# Underwater-Camera-v2_0.net
KiCad netlist of a schematic drawn in EAGLE
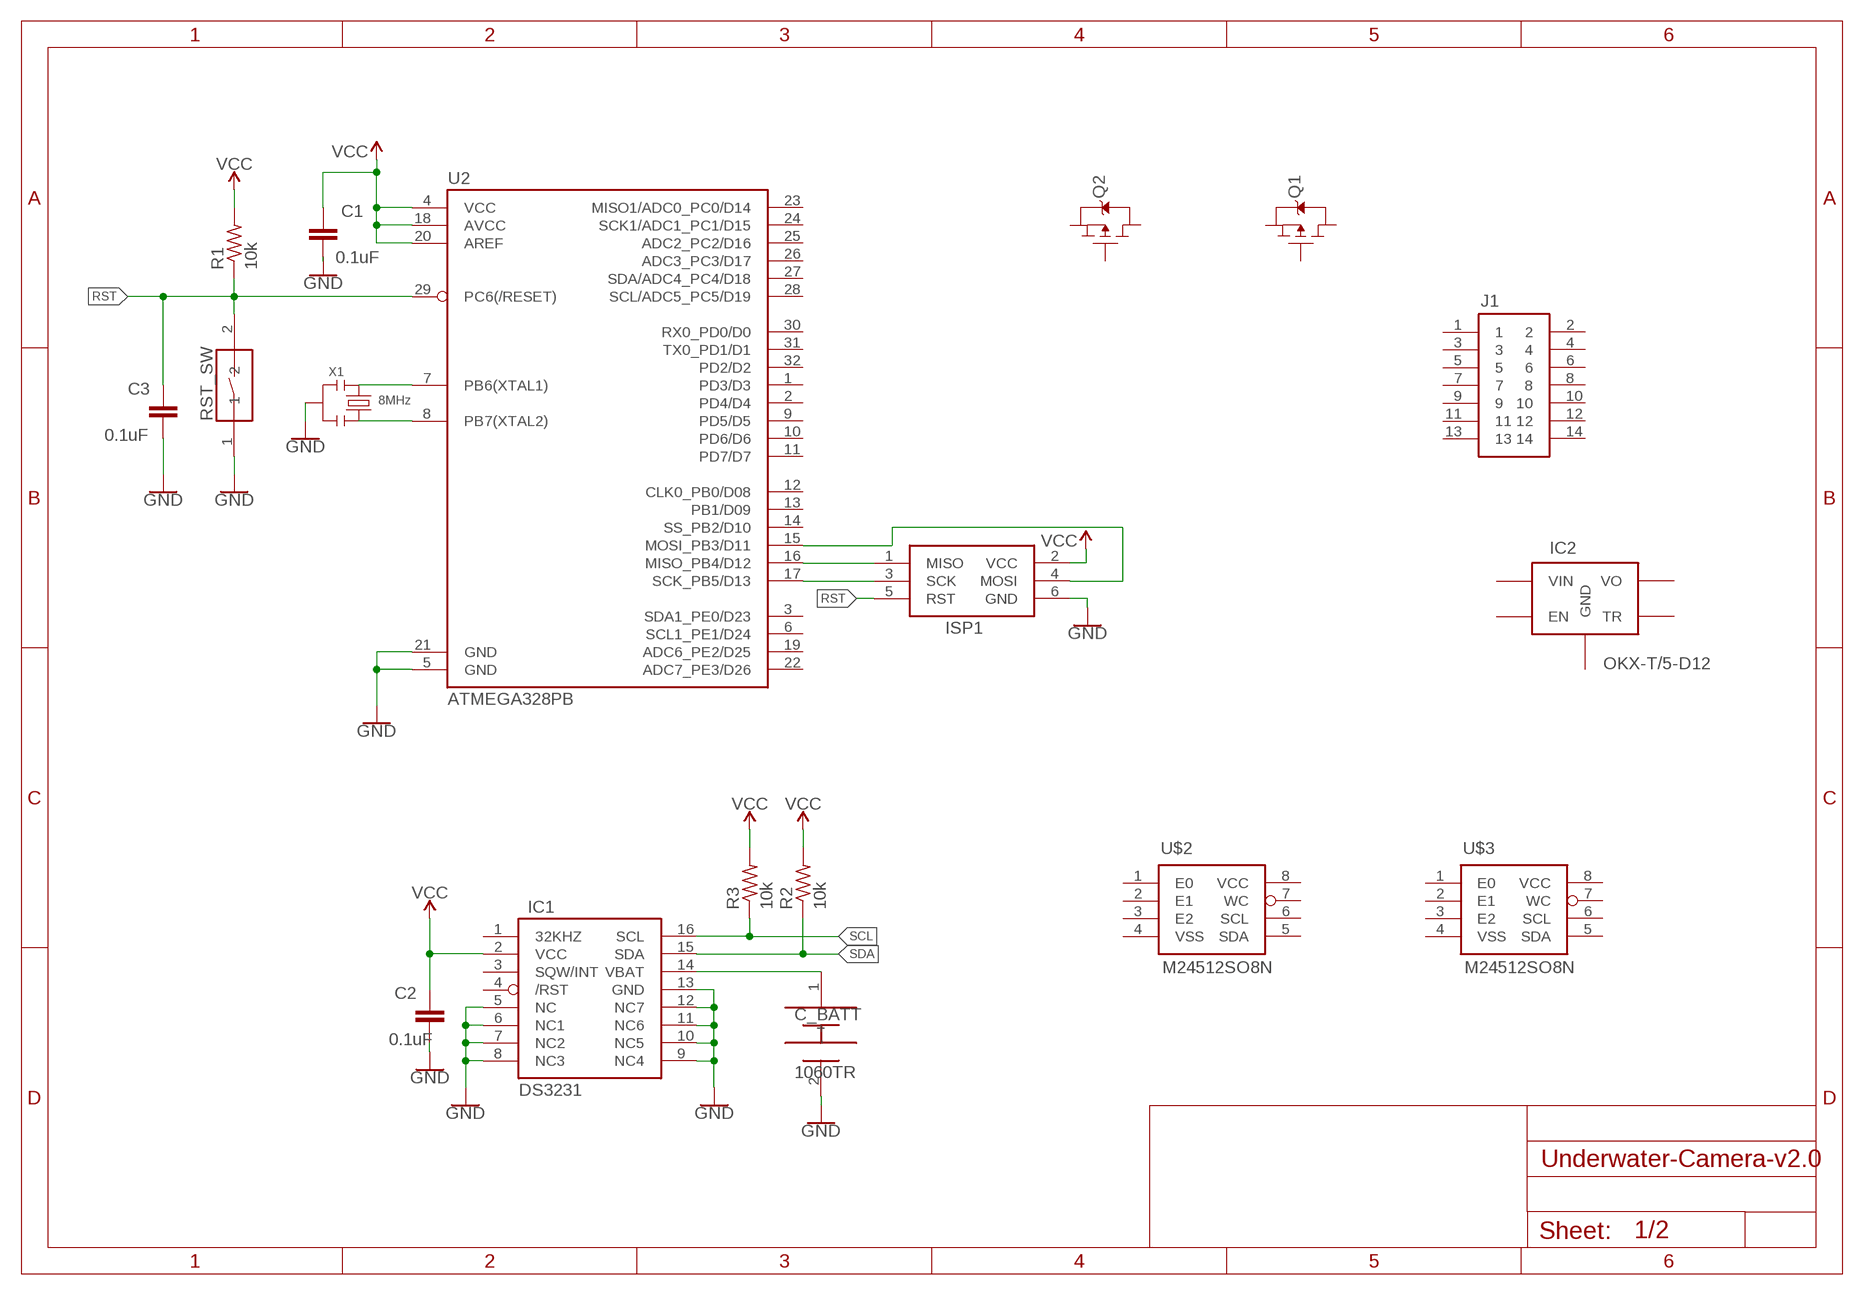
[diagram p0: schematic, sheet 1]
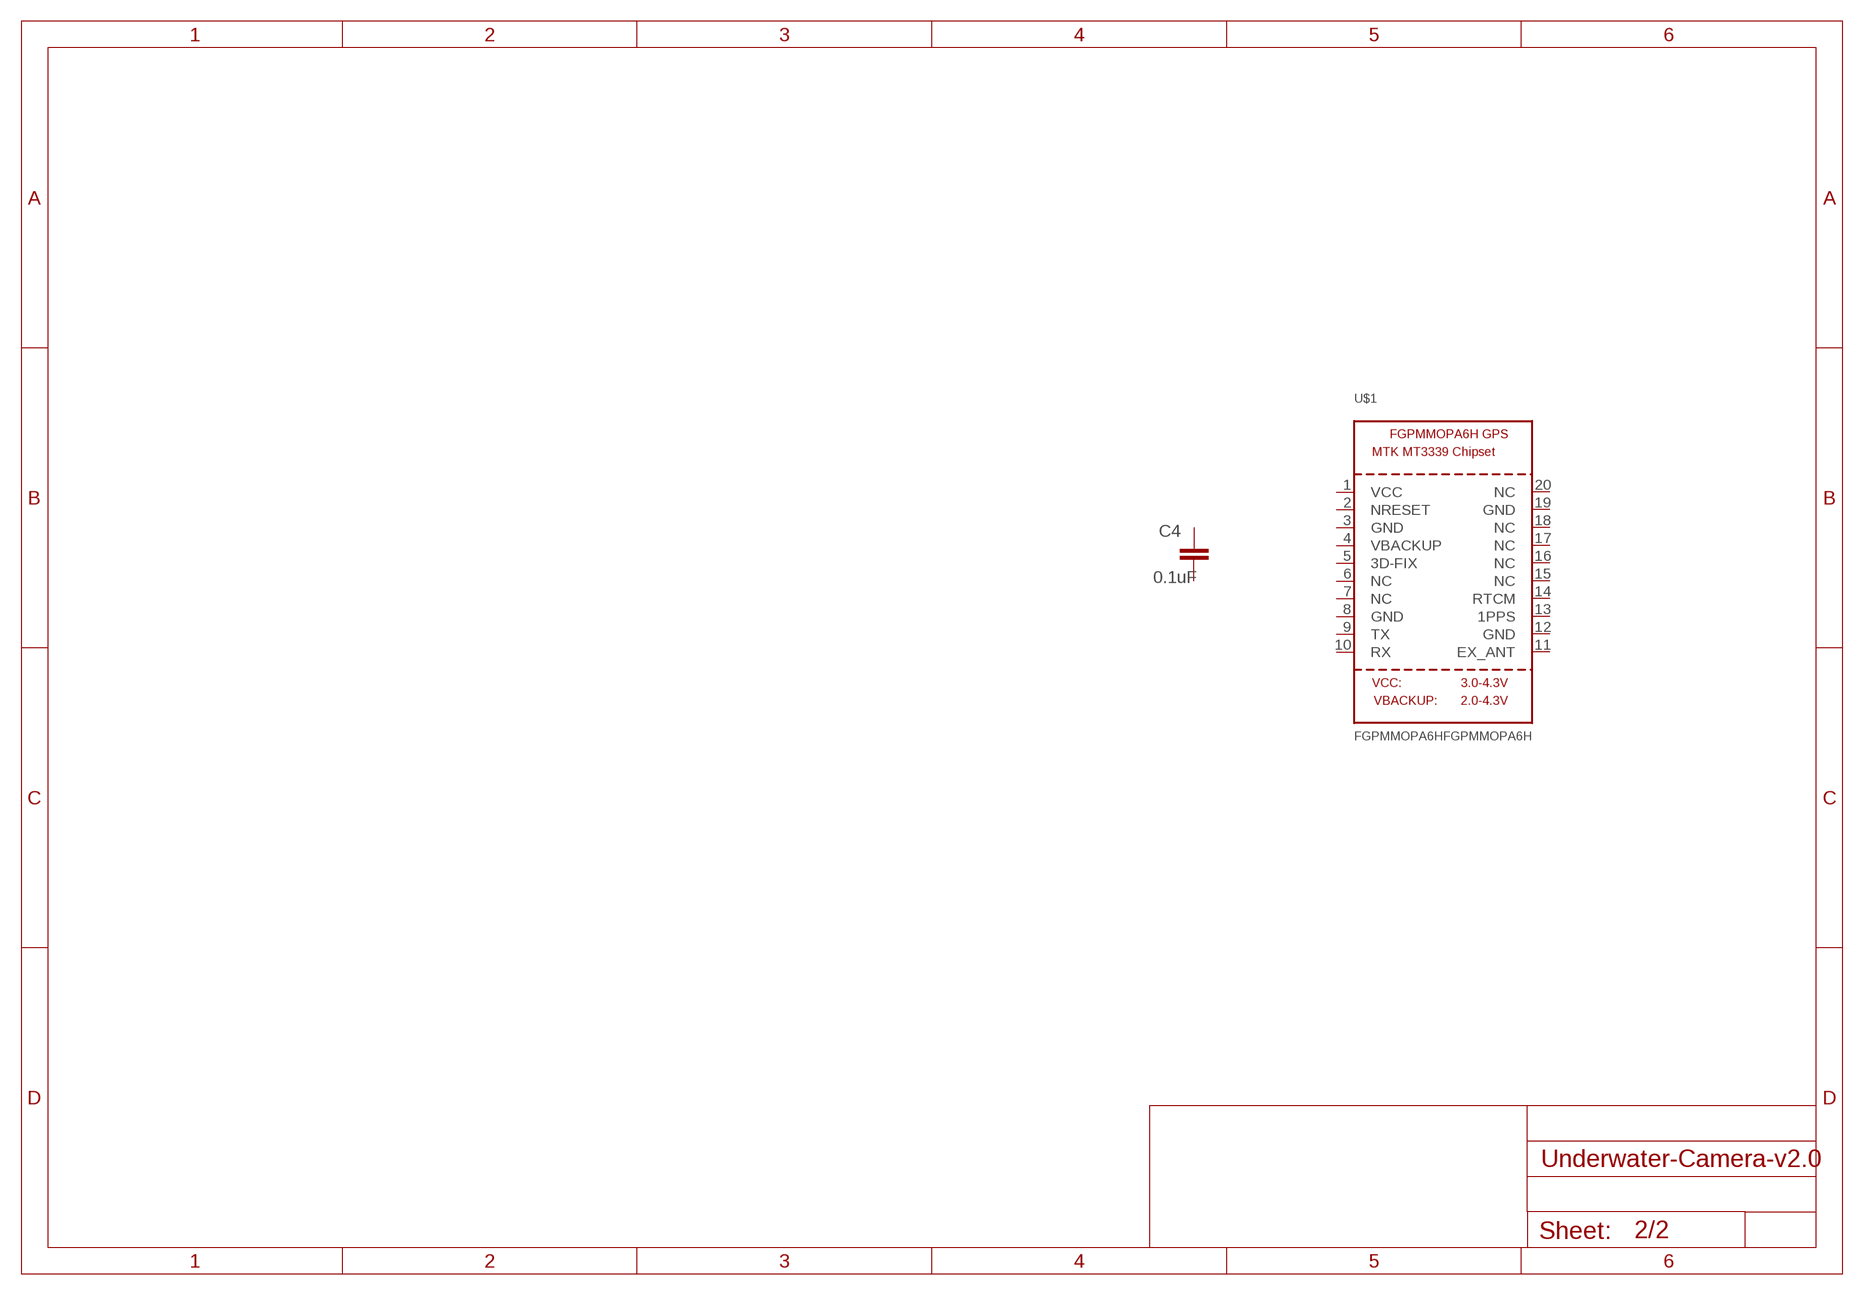
[diagram p1: schematic, sheet 2]

(export (version "E")
  (design (tool "Eeschema 10.0.6"))
  (components
    (comp (ref "C4")
      (value "0.1uF")
      (footprint "eagle-import:CAPC1608X50")
      (libsource (lib "eagle-import") (part "CAPACITOR_CERAMIC0603"))
    )
    (comp (ref "U$1")
      (value "FGPMMOPA6HFGPMMOPA6H")
      (footprint "eagle-import:SON150P1800X1800X500-20")
      (libsource (lib "eagle-import") (part "FGPMMOPA6HFGPMMOPA6H"))
    )
    (comp (ref "C1")
      (value "0.1uF")
      (footprint "eagle-import:CAPC1608X50")
      (libsource (lib "eagle-import") (part "CAPACITOR_CERAMIC0603"))
    )
    (comp (ref "C2")
      (value "0.1uF")
      (footprint "eagle-import:CAPC1608X50")
      (libsource (lib "eagle-import") (part "CAPACITOR_CERAMIC0603"))
    )
    (comp (ref "C3")
      (value "0.1uF")
      (footprint "eagle-import:CAPC1608X50")
      (libsource (lib "eagle-import") (part "CAPACITOR_CERAMIC0603"))
    )
    (comp (ref "C_BATT")
      (value "1060TR")
      (footprint "eagle-import:RESC26736X10")
      (libsource (lib "eagle-import") (part "1060TR"))
    )
    (comp (ref "IC1")
      (value "DS3231SOIC-16")
      (footprint "eagle-import:SOIC127P1135X265-16")
      (libsource (lib "eagle-import") (part "DS3231SOIC-16"))
    )
    (comp (ref "IC2")
      (value "OKX-T/5-D12")
      (footprint "eagle-import:HDRV9W64P254_1X9_2290X508X838B")
      (libsource (lib "eagle-import") (part "OKX-T/5-D12"))
    )
    (comp (ref "ISP1")
      (value "AVR_ISPHDR2X3")
      (footprint "eagle-import:HDRV6W64P254_2X3_1016X508X838B")
      (libsource (lib "eagle-import") (part "AVR_ISPHDR2X3"))
    )
    (comp (ref "J1")
      (value "HDR2X7HDR2X7")
      (footprint "eagle-import:HDRV14W64P254_2X7_1778X508X838B")
      (libsource (lib "eagle-import") (part "HDR2X7HDR2X7"))
    )
    (comp (ref "Q1")
      (value "DMG2305UXSOT23")
      (footprint "eagle-import:SOT95P240X110-3")
      (libsource (lib "eagle-import") (part "DMG2305UXSOT23"))
    )
    (comp (ref "Q2")
      (value "DMG2305UXSOT23")
      (footprint "eagle-import:SOT95P240X110-3")
      (libsource (lib "eagle-import") (part "DMG2305UXSOT23"))
    )
    (comp (ref "R1")
      (value "10k")
      (footprint "eagle-import:RESC1608X50")
      (libsource (lib "eagle-import") (part "RESISTOR0603"))
    )
    (comp (ref "R2")
      (value "10k")
      (footprint "eagle-import:RESC1608X50")
      (libsource (lib "eagle-import") (part "RESISTOR0603"))
    )
    (comp (ref "R3")
      (value "10k")
      (footprint "eagle-import:RESC1608X50")
      (libsource (lib "eagle-import") (part "RESISTOR0603"))
    )
    (comp (ref "RST_SW")
      (value "SWITCHB3U-1000P")
      (footprint "eagle-import:BEADC4225X160")
      (libsource (lib "eagle-import") (part "SWITCHB3U-1000P"))
    )
    (comp (ref "U$2")
      (value "M24512SO8N")
      (footprint "eagle-import:SOIC127P600X175-8")
      (libsource (lib "eagle-import") (part "M24512SO8N"))
    )
    (comp (ref "U$3")
      (value "M24512SO8N")
      (footprint "eagle-import:SOIC127P600X175-8")
      (libsource (lib "eagle-import") (part "M24512SO8N"))
    )
    (comp (ref "U2")
      (value "ATMEGA328PB")
      (footprint "eagle-import:QFP80P900X900X120-32")
      (libsource (lib "eagle-import") (part "ATMEGA328P"))
    )
    (comp (ref "X1")
      (value "8MHz")
      (footprint "eagle-import:RESCAXE120P320X130X70-6")
      (libsource (lib "eagle-import") (part "CERAMIC_RESONATOR"))
    )
  )
  (nets
    (net (code "1") (name "GND") (class "Default")
      (node (ref "C1") (pin "2") (pinfunction "2_2") (pintype "passive"))
      (node (ref "C2") (pin "2") (pinfunction "2_2") (pintype "passive"))
      (node (ref "C3") (pin "2") (pinfunction "2_2") (pintype "passive"))
      (node (ref "C_BATT") (pin "2") (pinfunction "-_2") (pintype "bidirectional"))
      (node (ref "IC1") (pin "10") (pinfunction "NC5_10") (pintype "bidirectional"))
      (node (ref "IC1") (pin "11") (pinfunction "NC6_11") (pintype "bidirectional"))
      (node (ref "IC1") (pin "12") (pinfunction "NC7_12") (pintype "bidirectional"))
      (node (ref "IC1") (pin "13") (pinfunction "GND_13") (pintype "power_in"))
      (node (ref "IC1") (pin "5") (pinfunction "NC_5") (pintype "bidirectional"))
      (node (ref "IC1") (pin "6") (pinfunction "NC1_6") (pintype "bidirectional"))
      (node (ref "IC1") (pin "7") (pinfunction "NC2_7") (pintype "bidirectional"))
      (node (ref "IC1") (pin "8") (pinfunction "NC3_8") (pintype "bidirectional"))
      (node (ref "IC1") (pin "9") (pinfunction "NC4_9") (pintype "bidirectional"))
      (node (ref "ISP1") (pin "6") (pinfunction "GND_6") (pintype "power_in"))
      (node (ref "RST_SW") (pin "1") (pinfunction "1_1") (pintype "passive"))
      (node (ref "U2") (pin "21") (pinfunction "GND_21") (pintype "bidirectional"))
      (node (ref "U2") (pin "5") (pinfunction "GND_5") (pintype "bidirectional"))
      (node (ref "X1") (pin "2") (pinfunction "2_2") (pintype "passive"))
      (node (ref "X1") (pin "5") (pinfunction "2_5") (pintype "passive"))
    )
    (net (code "2") (name "Net-(C_BATT-+)") (class "Default")
      (node (ref "C_BATT") (pin "1") (pinfunction "+_1") (pintype "bidirectional"))
      (node (ref "IC1") (pin "14") (pinfunction "VBAT_14") (pintype "power_in"))
    )
    (net (code "3") (name "Net-(ISP1-MISO)") (class "Default")
      (node (ref "ISP1") (pin "1") (pinfunction "MISO_1") (pintype "input"))
      (node (ref "U2") (pin "16") (pinfunction "MISO_PB4/D12_16") (pintype "bidirectional"))
    )
    (net (code "4") (name "Net-(ISP1-MOSI)") (class "Default")
      (node (ref "ISP1") (pin "4") (pinfunction "MOSI_4") (pintype "output"))
      (node (ref "U2") (pin "15") (pinfunction "MOSI_PB3/D11_15") (pintype "bidirectional"))
    )
    (net (code "5") (name "Net-(ISP1-SCK)") (class "Default")
      (node (ref "ISP1") (pin "3") (pinfunction "SCK_3") (pintype "output"))
      (node (ref "U2") (pin "17") (pinfunction "SCK_PB5/D13_17") (pintype "bidirectional"))
    )
    (net (code "6") (name "Net-(U2-PB6(XTAL1))") (class "Default")
      (node (ref "U2") (pin "7") (pinfunction "PB6(XTAL1)_7") (pintype "bidirectional"))
      (node (ref "X1") (pin "1") (pinfunction "1_1") (pintype "passive"))
      (node (ref "X1") (pin "6") (pinfunction "1_6") (pintype "passive"))
    )
    (net (code "7") (name "Net-(U2-PB7(XTAL2))") (class "Default")
      (node (ref "U2") (pin "8") (pinfunction "PB7(XTAL2)_8") (pintype "bidirectional"))
      (node (ref "X1") (pin "3") (pinfunction "3_3") (pintype "passive"))
      (node (ref "X1") (pin "4") (pinfunction "3_4") (pintype "passive"))
    )
    (net (code "8") (name "RST") (class "Default")
      (node (ref "C3") (pin "1") (pinfunction "1_1") (pintype "passive"))
      (node (ref "ISP1") (pin "5") (pinfunction "RST_5") (pintype "output"))
      (node (ref "R1") (pin "1") (pinfunction "1_1") (pintype "passive"))
      (node (ref "RST_SW") (pin "2") (pinfunction "2_2") (pintype "passive"))
      (node (ref "U2") (pin "29") (pinfunction "PC6(/RESET)_29") (pintype "bidirectional"))
    )
    (net (code "9") (name "SCL") (class "Default")
      (node (ref "IC1") (pin "16") (pinfunction "SCL_16") (pintype "bidirectional"))
      (node (ref "R3") (pin "1") (pinfunction "1_1") (pintype "passive"))
    )
    (net (code "10") (name "SDA") (class "Default")
      (node (ref "IC1") (pin "15") (pinfunction "SDA_15") (pintype "bidirectional"))
      (node (ref "R2") (pin "1") (pinfunction "1_1") (pintype "passive"))
    )
    (net (code "11") (name "VCC") (class "Default")
      (node (ref "C1") (pin "1") (pinfunction "1_1") (pintype "passive"))
      (node (ref "C2") (pin "1") (pinfunction "1_1") (pintype "passive"))
      (node (ref "IC1") (pin "2") (pinfunction "VCC_2") (pintype "power_in"))
      (node (ref "ISP1") (pin "2") (pinfunction "VCC_2") (pintype "power_in"))
      (node (ref "R1") (pin "2") (pinfunction "2_2") (pintype "passive"))
      (node (ref "R2") (pin "2") (pinfunction "2_2") (pintype "passive"))
      (node (ref "R3") (pin "2") (pinfunction "2_2") (pintype "passive"))
      (node (ref "U2") (pin "18") (pinfunction "AVCC_18") (pintype "bidirectional"))
      (node (ref "U2") (pin "20") (pinfunction "AREF_20") (pintype "bidirectional"))
      (node (ref "U2") (pin "4") (pinfunction "VCC_4") (pintype "bidirectional"))
    )
    (net (code "12") (name "unconnected-(C4-Pad1)") (class "Default")
      (node (ref "C4") (pin "1") (pinfunction "1_1") (pintype "passive"))
    )
    (net (code "13") (name "unconnected-(C4-Pad2)") (class "Default")
      (node (ref "C4") (pin "2") (pinfunction "2_2") (pintype "passive"))
    )
    (net (code "14") (name "unconnected-(IC1-32KHZ-Pad1)") (class "Default")
      (node (ref "IC1") (pin "1") (pinfunction "32KHZ_1") (pintype "output"))
    )
    (net (code "15") (name "unconnected-(IC1-SQW{slash}INT-Pad3)") (class "Default")
      (node (ref "IC1") (pin "3") (pinfunction "SQW/INT_3") (pintype "output"))
    )
    (net (code "16") (name "unconnected-(IC1-{slash}RST-Pad4)") (class "Default")
      (node (ref "IC1") (pin "4") (pinfunction "/RST_4") (pintype "passive"))
    )
    (net (code "17") (name "unconnected-(IC2-EN-Pad9)") (class "Default")
      (node (ref "IC2") (pin "9") (pinfunction "EN_9") (pintype "bidirectional"))
    )
    (net (code "18") (name "unconnected-(IC2-GND-Pad3)") (class "Default")
      (node (ref "IC2") (pin "3") (pinfunction "GND_3") (pintype "bidirectional"))
    )
    (net (code "19") (name "unconnected-(IC2-TR-Pad2)") (class "Default")
      (node (ref "IC2") (pin "2") (pinfunction "TR_2") (pintype "bidirectional"))
    )
    (net (code "20") (name "unconnected-(IC2-VIN-Pad8)") (class "Default")
      (node (ref "IC2") (pin "8") (pinfunction "VIN_8") (pintype "bidirectional"))
    )
    (net (code "21") (name "unconnected-(IC2-VO-Pad1)") (class "Default")
      (node (ref "IC2") (pin "1") (pinfunction "VO_1") (pintype "bidirectional"))
    )
    (net (code "22") (name "unconnected-(J1-Pad1)") (class "Default")
      (node (ref "J1") (pin "1") (pinfunction "1_1") (pintype "bidirectional"))
    )
    (net (code "23") (name "unconnected-(J1-Pad2)") (class "Default")
      (node (ref "J1") (pin "2") (pinfunction "2_2") (pintype "bidirectional"))
    )
    (net (code "24") (name "unconnected-(J1-Pad3)") (class "Default")
      (node (ref "J1") (pin "3") (pinfunction "3_3") (pintype "bidirectional"))
    )
    (net (code "25") (name "unconnected-(J1-Pad4)") (class "Default")
      (node (ref "J1") (pin "4") (pinfunction "4_4") (pintype "bidirectional"))
    )
    (net (code "26") (name "unconnected-(J1-Pad5)") (class "Default")
      (node (ref "J1") (pin "5") (pinfunction "5_5") (pintype "bidirectional"))
    )
    (net (code "27") (name "unconnected-(J1-Pad6)") (class "Default")
      (node (ref "J1") (pin "6") (pinfunction "6_6") (pintype "bidirectional"))
    )
    (net (code "28") (name "unconnected-(J1-Pad7)") (class "Default")
      (node (ref "J1") (pin "7") (pinfunction "7_7") (pintype "bidirectional"))
    )
    (net (code "29") (name "unconnected-(J1-Pad8)") (class "Default")
      (node (ref "J1") (pin "8") (pinfunction "8_8") (pintype "bidirectional"))
    )
    (net (code "30") (name "unconnected-(J1-Pad9)") (class "Default")
      (node (ref "J1") (pin "9") (pinfunction "9_9") (pintype "bidirectional"))
    )
    (net (code "31") (name "unconnected-(J1-Pad10)") (class "Default")
      (node (ref "J1") (pin "10") (pinfunction "10_10") (pintype "bidirectional"))
    )
    (net (code "32") (name "unconnected-(J1-Pad11)") (class "Default")
      (node (ref "J1") (pin "11") (pinfunction "11_11") (pintype "bidirectional"))
    )
    (net (code "33") (name "unconnected-(J1-Pad12)") (class "Default")
      (node (ref "J1") (pin "12") (pinfunction "12_12") (pintype "bidirectional"))
    )
    (net (code "34") (name "unconnected-(J1-Pad13)") (class "Default")
      (node (ref "J1") (pin "13") (pinfunction "13_13") (pintype "bidirectional"))
    )
    (net (code "35") (name "unconnected-(J1-Pad14)") (class "Default")
      (node (ref "J1") (pin "14") (pinfunction "14_14") (pintype "bidirectional"))
    )
    (net (code "36") (name "unconnected-(Q1-D-Pad3)") (class "Default")
      (node (ref "Q1") (pin "3") (pinfunction "D_3") (pintype "bidirectional"))
    )
    (net (code "37") (name "unconnected-(Q1-G-Pad1)") (class "Default")
      (node (ref "Q1") (pin "1") (pinfunction "G_1") (pintype "bidirectional"))
    )
    (net (code "38") (name "unconnected-(Q1-S-Pad2)") (class "Default")
      (node (ref "Q1") (pin "2") (pinfunction "S_2") (pintype "bidirectional"))
    )
    (net (code "39") (name "unconnected-(Q2-D-Pad3)") (class "Default")
      (node (ref "Q2") (pin "3") (pinfunction "D_3") (pintype "bidirectional"))
    )
    (net (code "40") (name "unconnected-(Q2-G-Pad1)") (class "Default")
      (node (ref "Q2") (pin "1") (pinfunction "G_1") (pintype "bidirectional"))
    )
    (net (code "41") (name "unconnected-(Q2-S-Pad2)") (class "Default")
      (node (ref "Q2") (pin "2") (pinfunction "S_2") (pintype "bidirectional"))
    )
    (net (code "42") (name "unconnected-(U$1-1PPS-Pad13)") (class "Default")
      (node (ref "U$1") (pin "13") (pinfunction "1PPS_13") (pintype "bidirectional"))
    )
    (net (code "43") (name "unconnected-(U$1-3D-FIX-Pad5)") (class "Default")
      (node (ref "U$1") (pin "5") (pinfunction "3D-FIX_5") (pintype "bidirectional"))
    )
    (net (code "44") (name "unconnected-(U$1-EX_ANT-Pad11)") (class "Default")
      (node (ref "U$1") (pin "11") (pinfunction "EX_ANT_11") (pintype "bidirectional"))
    )
    (net (code "45") (name "unconnected-(U$1-GND-Pad3)") (class "Default")
      (node (ref "U$1") (pin "3") (pinfunction "GND_3") (pintype "bidirectional"))
    )
    (net (code "46") (name "unconnected-(U$1-GND-Pad8)") (class "Default")
      (node (ref "U$1") (pin "8") (pinfunction "GND_8") (pintype "bidirectional"))
    )
    (net (code "47") (name "unconnected-(U$1-GND-Pad12)") (class "Default")
      (node (ref "U$1") (pin "12") (pinfunction "GND_12") (pintype "bidirectional"))
    )
    (net (code "48") (name "unconnected-(U$1-GND-Pad19)") (class "Default")
      (node (ref "U$1") (pin "19") (pinfunction "GND_19") (pintype "bidirectional"))
    )
    (net (code "49") (name "unconnected-(U$1-NC-Pad6)") (class "Default")
      (node (ref "U$1") (pin "6") (pinfunction "NC_6") (pintype "bidirectional"))
    )
    (net (code "50") (name "unconnected-(U$1-NC-Pad7)") (class "Default")
      (node (ref "U$1") (pin "7") (pinfunction "NC_7") (pintype "bidirectional"))
    )
    (net (code "51") (name "unconnected-(U$1-NC-Pad15)") (class "Default")
      (node (ref "U$1") (pin "15") (pinfunction "NC_15") (pintype "bidirectional"))
    )
    (net (code "52") (name "unconnected-(U$1-NC-Pad16)") (class "Default")
      (node (ref "U$1") (pin "16") (pinfunction "NC_16") (pintype "bidirectional"))
    )
    (net (code "53") (name "unconnected-(U$1-NC-Pad17)") (class "Default")
      (node (ref "U$1") (pin "17") (pinfunction "NC_17") (pintype "bidirectional"))
    )
    (net (code "54") (name "unconnected-(U$1-NC-Pad18)") (class "Default")
      (node (ref "U$1") (pin "18") (pinfunction "NC_18") (pintype "bidirectional"))
    )
    (net (code "55") (name "unconnected-(U$1-NC-Pad20)") (class "Default")
      (node (ref "U$1") (pin "20") (pinfunction "NC_20") (pintype "bidirectional"))
    )
    (net (code "56") (name "unconnected-(U$1-NRESET-Pad2)") (class "Default")
      (node (ref "U$1") (pin "2") (pinfunction "NRESET_2") (pintype "bidirectional"))
    )
    (net (code "57") (name "unconnected-(U$1-RTCM-Pad14)") (class "Default")
      (node (ref "U$1") (pin "14") (pinfunction "RTCM_14") (pintype "bidirectional"))
    )
    (net (code "58") (name "unconnected-(U$1-RX-Pad10)") (class "Default")
      (node (ref "U$1") (pin "10") (pinfunction "RX_10") (pintype "bidirectional"))
    )
    (net (code "59") (name "unconnected-(U$1-TX-Pad9)") (class "Default")
      (node (ref "U$1") (pin "9") (pinfunction "TX_9") (pintype "bidirectional"))
    )
    (net (code "60") (name "unconnected-(U$1-VBACKUP-Pad4)") (class "Default")
      (node (ref "U$1") (pin "4") (pinfunction "VBACKUP_4") (pintype "bidirectional"))
    )
    (net (code "61") (name "unconnected-(U$1-VCC-Pad1)") (class "Default")
      (node (ref "U$1") (pin "1") (pinfunction "VCC_1") (pintype "bidirectional"))
    )
    (net (code "62") (name "unconnected-(U$2-E0-Pad1)") (class "Default")
      (node (ref "U$2") (pin "1") (pinfunction "E0_1") (pintype "bidirectional"))
    )
    (net (code "63") (name "unconnected-(U$2-E1-Pad2)") (class "Default")
      (node (ref "U$2") (pin "2") (pinfunction "E1_2") (pintype "bidirectional"))
    )
    (net (code "64") (name "unconnected-(U$2-E2-Pad3)") (class "Default")
      (node (ref "U$2") (pin "3") (pinfunction "E2_3") (pintype "bidirectional"))
    )
    (net (code "65") (name "unconnected-(U$2-SCL-Pad6)") (class "Default")
      (node (ref "U$2") (pin "6") (pinfunction "SCL_6") (pintype "bidirectional"))
    )
    (net (code "66") (name "unconnected-(U$2-SDA-Pad5)") (class "Default")
      (node (ref "U$2") (pin "5") (pinfunction "SDA_5") (pintype "bidirectional"))
    )
    (net (code "67") (name "unconnected-(U$2-VCC-Pad8)") (class "Default")
      (node (ref "U$2") (pin "8") (pinfunction "VCC_8") (pintype "bidirectional"))
    )
    (net (code "68") (name "unconnected-(U$2-VSS-Pad4)") (class "Default")
      (node (ref "U$2") (pin "4") (pinfunction "VSS_4") (pintype "bidirectional"))
    )
    (net (code "69") (name "unconnected-(U$2-WC-Pad7)") (class "Default")
      (node (ref "U$2") (pin "7") (pinfunction "WC_7") (pintype "bidirectional"))
    )
    (net (code "70") (name "unconnected-(U$3-E0-Pad1)") (class "Default")
      (node (ref "U$3") (pin "1") (pinfunction "E0_1") (pintype "bidirectional"))
    )
    (net (code "71") (name "unconnected-(U$3-E1-Pad2)") (class "Default")
      (node (ref "U$3") (pin "2") (pinfunction "E1_2") (pintype "bidirectional"))
    )
    (net (code "72") (name "unconnected-(U$3-E2-Pad3)") (class "Default")
      (node (ref "U$3") (pin "3") (pinfunction "E2_3") (pintype "bidirectional"))
    )
    (net (code "73") (name "unconnected-(U$3-SCL-Pad6)") (class "Default")
      (node (ref "U$3") (pin "6") (pinfunction "SCL_6") (pintype "bidirectional"))
    )
    (net (code "74") (name "unconnected-(U$3-SDA-Pad5)") (class "Default")
      (node (ref "U$3") (pin "5") (pinfunction "SDA_5") (pintype "bidirectional"))
    )
    (net (code "75") (name "unconnected-(U$3-VCC-Pad8)") (class "Default")
      (node (ref "U$3") (pin "8") (pinfunction "VCC_8") (pintype "bidirectional"))
    )
    (net (code "76") (name "unconnected-(U$3-VSS-Pad4)") (class "Default")
      (node (ref "U$3") (pin "4") (pinfunction "VSS_4") (pintype "bidirectional"))
    )
    (net (code "77") (name "unconnected-(U$3-WC-Pad7)") (class "Default")
      (node (ref "U$3") (pin "7") (pinfunction "WC_7") (pintype "bidirectional"))
    )
    (net (code "78") (name "unconnected-(U2-ADC2_PC2{slash}D16-Pad25)") (class "Default")
      (node (ref "U2") (pin "25") (pinfunction "ADC2_PC2/D16_25") (pintype "bidirectional"))
    )
    (net (code "79") (name "unconnected-(U2-ADC3_PC3{slash}D17-Pad26)") (class "Default")
      (node (ref "U2") (pin "26") (pinfunction "ADC3_PC3/D17_26") (pintype "bidirectional"))
    )
    (net (code "80") (name "unconnected-(U2-ADC6_PE2{slash}D25-Pad19)") (class "Default")
      (node (ref "U2") (pin "19") (pinfunction "ADC6_PE2/D25_19") (pintype "bidirectional"))
    )
    (net (code "81") (name "unconnected-(U2-ADC7_PE3{slash}D26-Pad22)") (class "Default")
      (node (ref "U2") (pin "22") (pinfunction "ADC7_PE3/D26_22") (pintype "bidirectional"))
    )
    (net (code "82") (name "unconnected-(U2-CLK0_PB0{slash}D08-Pad12)") (class "Default")
      (node (ref "U2") (pin "12") (pinfunction "CLK0_PB0/D08_12") (pintype "bidirectional"))
    )
    (net (code "83") (name "unconnected-(U2-MISO1{slash}ADC0_PC0{slash}D14-Pad23)") (class "Default")
      (node (ref "U2") (pin "23") (pinfunction "MISO1/ADC0_PC0/D14_23") (pintype "bidirectional"))
    )
    (net (code "84") (name "unconnected-(U2-PB1{slash}D09-Pad13)") (class "Default")
      (node (ref "U2") (pin "13") (pinfunction "PB1/D09_13") (pintype "bidirectional"))
    )
    (net (code "85") (name "unconnected-(U2-PD2{slash}D2-Pad32)") (class "Default")
      (node (ref "U2") (pin "32") (pinfunction "PD2/D2_32") (pintype "bidirectional"))
    )
    (net (code "86") (name "unconnected-(U2-PD3{slash}D3-Pad1)") (class "Default")
      (node (ref "U2") (pin "1") (pinfunction "PD3/D3_1") (pintype "bidirectional"))
    )
    (net (code "87") (name "unconnected-(U2-PD4{slash}D4-Pad2)") (class "Default")
      (node (ref "U2") (pin "2") (pinfunction "PD4/D4_2") (pintype "bidirectional"))
    )
    (net (code "88") (name "unconnected-(U2-PD5{slash}D5-Pad9)") (class "Default")
      (node (ref "U2") (pin "9") (pinfunction "PD5/D5_9") (pintype "bidirectional"))
    )
    (net (code "89") (name "unconnected-(U2-PD6{slash}D6-Pad10)") (class "Default")
      (node (ref "U2") (pin "10") (pinfunction "PD6/D6_10") (pintype "bidirectional"))
    )
    (net (code "90") (name "unconnected-(U2-PD7{slash}D7-Pad11)") (class "Default")
      (node (ref "U2") (pin "11") (pinfunction "PD7/D7_11") (pintype "bidirectional"))
    )
    (net (code "91") (name "unconnected-(U2-RX0_PD0{slash}D0-Pad30)") (class "Default")
      (node (ref "U2") (pin "30") (pinfunction "RX0_PD0/D0_30") (pintype "bidirectional"))
    )
    (net (code "92") (name "unconnected-(U2-SCK1{slash}ADC1_PC1{slash}D15-Pad24)") (class "Default")
      (node (ref "U2") (pin "24") (pinfunction "SCK1/ADC1_PC1/D15_24") (pintype "bidirectional"))
    )
    (net (code "93") (name "unconnected-(U2-SCL1_PE1{slash}D24-Pad6)") (class "Default")
      (node (ref "U2") (pin "6") (pinfunction "SCL1_PE1/D24_6") (pintype "bidirectional"))
    )
    (net (code "94") (name "unconnected-(U2-SCL{slash}ADC5_PC5{slash}D19-Pad28)") (class "Default")
      (node (ref "U2") (pin "28") (pinfunction "SCL/ADC5_PC5/D19_28") (pintype "bidirectional"))
    )
    (net (code "95") (name "unconnected-(U2-SDA1_PE0{slash}D23-Pad3)") (class "Default")
      (node (ref "U2") (pin "3") (pinfunction "SDA1_PE0/D23_3") (pintype "bidirectional"))
    )
    (net (code "96") (name "unconnected-(U2-SDA{slash}ADC4_PC4{slash}D18-Pad27)") (class "Default")
      (node (ref "U2") (pin "27") (pinfunction "SDA/ADC4_PC4/D18_27") (pintype "bidirectional"))
    )
    (net (code "97") (name "unconnected-(U2-SS_PB2{slash}D10-Pad14)") (class "Default")
      (node (ref "U2") (pin "14") (pinfunction "SS_PB2/D10_14") (pintype "bidirectional"))
    )
    (net (code "98") (name "unconnected-(U2-TX0_PD1{slash}D1-Pad31)") (class "Default")
      (node (ref "U2") (pin "31") (pinfunction "TX0_PD1/D1_31") (pintype "bidirectional"))
    )
  )
)
